# DualUSB2_0_CON.net
KiCad netlist of a schematic drawn in Altium Designer
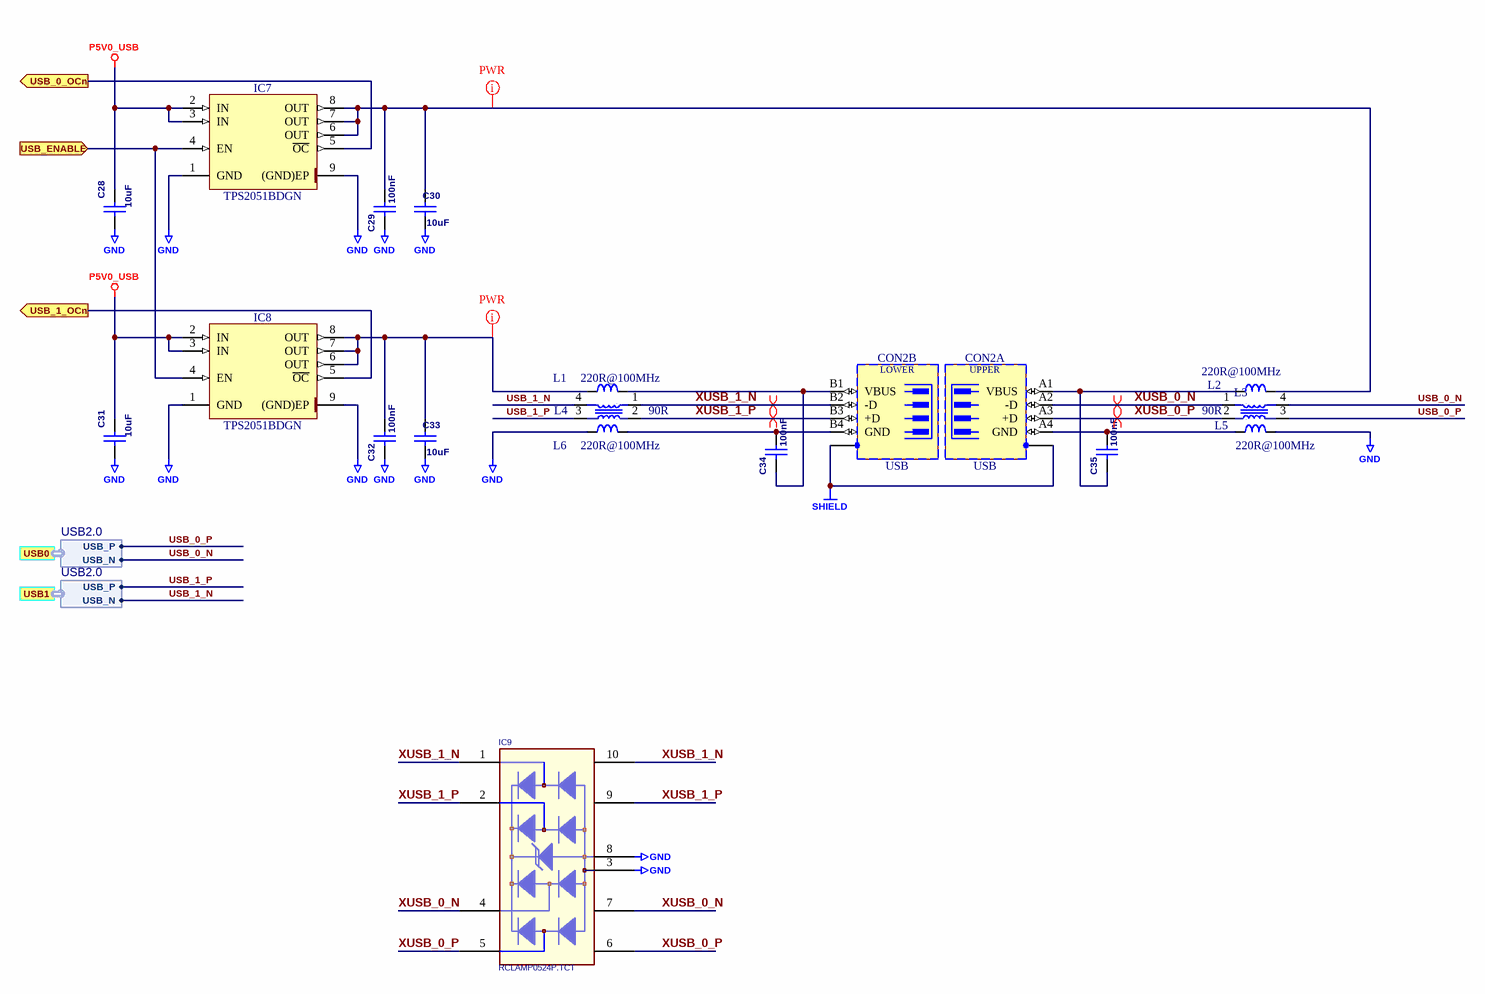
[diagram p0: DualUSB2.0_CON.SchDoc]

(export (version "E")
  (design (tool "Eeschema 10.0.6"))
  (components
    (comp (ref "C28")
      (value "10uF")
      (footprint "CAPC2012X135N")
      (description "Non-polarised capacitor")
      (fields
        (field (name "PART NUMBER") "CC0805_10UF_10V_10%_X7R")
        (field (name "VOLTAGE") "10V")
        (field (name "AUTHOR") "CERN DEM JLC")
      )
      (libsource (lib "Capacitors") (part "Capacitor - non polarized"))
    )
    (comp (ref "C29")
      (value "100nF")
      (footprint "CAPC1005X55N")
      (description "Non-polarised capacitor")
      (fields
        (field (name "PART NUMBER") "CC0402_100NF_16V_10%_X7R")
        (field (name "VOLTAGE") "16V")
        (field (name "AUTHOR") "CERN DEM JLC")
      )
      (libsource (lib "Capacitors") (part "Capacitor - non polarized"))
    )
    (comp (ref "C30")
      (value "10uF")
      (footprint "CAPC2012X135N")
      (description "Non-polarised capacitor")
      (fields
        (field (name "PART NUMBER") "CC0805_10UF_10V_10%_X7R")
        (field (name "VOLTAGE") "10V")
        (field (name "AUTHOR") "CERN DEM JLC")
      )
      (libsource (lib "Capacitors") (part "Capacitor - non polarized"))
    )
    (comp (ref "C31")
      (value "10uF")
      (footprint "CAPC2012X135N")
      (description "Non-polarised capacitor")
      (fields
        (field (name "PART NUMBER") "CC0805_10UF_10V_10%_X7R")
        (field (name "VOLTAGE") "10V")
        (field (name "AUTHOR") "CERN DEM JLC")
      )
      (libsource (lib "Capacitors") (part "Capacitor - non polarized"))
    )
    (comp (ref "C32")
      (value "100nF")
      (footprint "CAPC1005X55N")
      (description "Non-polarised capacitor")
      (fields
        (field (name "PART NUMBER") "CC0402_100NF_16V_10%_X7R")
        (field (name "VOLTAGE") "16V")
        (field (name "AUTHOR") "CERN DEM JLC")
      )
      (libsource (lib "Capacitors") (part "Capacitor - non polarized"))
    )
    (comp (ref "C33")
      (value "10uF")
      (footprint "CAPC2012X135N")
      (description "Non-polarised capacitor")
      (fields
        (field (name "PART NUMBER") "CC0805_10UF_10V_10%_X7R")
        (field (name "VOLTAGE") "10V")
        (field (name "AUTHOR") "CERN DEM JLC")
      )
      (libsource (lib "Capacitors") (part "Capacitor - non polarized"))
    )
    (comp (ref "C34")
      (value "100nF")
      (footprint "CAPC1005X55N")
      (description "Non-polarised capacitor")
      (fields
        (field (name "PART NUMBER") "CC0402_100NF_16V_10%_X7R")
        (field (name "VOLTAGE") "16V")
        (field (name "AUTHOR") "CERN DEM JLC")
      )
      (libsource (lib "Capacitors") (part "Capacitor - non polarized"))
    )
    (comp (ref "C35")
      (value "100nF")
      (footprint "CAPC1005X55N")
      (description "Non-polarised capacitor")
      (fields
        (field (name "PART NUMBER") "CC0402_100NF_16V_10%_X7R")
        (field (name "VOLTAGE") "16V")
        (field (name "AUTHOR") "CERN DEM JLC")
      )
      (libsource (lib "Capacitors") (part "Capacitor - non polarized"))
    )
    (comp (ref "CON2")
      (value "USB")
      (footprint "FCI_72309-8034BLF")
      (description "Dual 4 Pin + 1 Shield USB Receptacle")
      (fields
        (field (name "PART NUMBER") "FCI_72309-8034BLF")
        (field (name "MANUFACTURER") "FCI")
        (field (name "AUTHOR") "CERN DEM JLC")
      )
      (libsource (lib "Connectors") (part "Connector USBx2 4 Pin + 1Shield"))
    )
    (comp (ref "IC7")
      (value "TPS2051BDGN")
      (footprint "SOP65P490X110-9N-R157X189")
      (description "One Channel, Current-Limited, Power-Distribution Switches")
      (fields (field (name "MANUFACTURER") "TEXAS INSTRUMENTS") (field (name "AUTHOR") "CERN DEM BC"))
      (libsource (lib "ICs And Semiconductors") (part "TPS2051BDGN"))
    )
    (comp (ref "IC8")
      (value "TPS2051BDGN")
      (footprint "SOP65P490X110-9N-R157X189")
      (description "One Channel, Current-Limited, Power-Distribution Switches")
      (fields (field (name "MANUFACTURER") "TEXAS INSTRUMENTS") (field (name "AUTHOR") "CERN DEM BC"))
      (libsource (lib "ICs And Semiconductors") (part "TPS2051BDGN"))
    )
    (comp (ref "IC9")
      (value "RCLAMP0524P.TCT")
      (description "DIODE,RCLAMP0524P,SEMTECH")
      (libsource (lib "LIBRARY_SCH") (part "D_TVS_RCLAMP0524P"))
    )
    (comp (ref "L1")
      (value "220R@100MHz")
      (footprint "INDC2012X105N")
      (description "Inductor")
      (fields
        (field (name "PART NUMBER") "IND0805_MURATA_BLM21PG221SN1D")
        (field (name "POWER") "2A")
        (field (name "AUTHOR") "CERN DEM JLC")
      )
      (libsource (lib "Inductors & Transformers") (part "Inductor"))
    )
    (comp (ref "L2")
      (value "220R@100MHz")
      (footprint "INDC2012X105N")
      (description "Inductor")
      (fields
        (field (name "PART NUMBER") "IND0805_MURATA_BLM21PG221SN1D")
        (field (name "POWER") "2A")
        (field (name "AUTHOR") "CERN DEM JLC")
      )
      (libsource (lib "Inductors & Transformers") (part "Inductor"))
    )
    (comp (ref "L3")
      (value "90R")
      (footprint "DLSCM0805")
      (description "Common Mode Choke 90R")
      (fields (field (name "Comment") "DLSCM0805-900M or DLW21SN900SQ2L"))
      (libsource (lib "") (part "L_CMC_DLSCM0805_90R_1"))
    )
    (comp (ref "L4")
      (value "90R")
      (footprint "DLSCM0805")
      (description "Common Mode Choke 90R")
      (fields (field (name "Comment") "DLSCM0805-900M or DLW21SN900SQ2L"))
      (libsource (lib "LIBRARY_SCH") (part "L_CMC_DLSCM0805_90R"))
    )
    (comp (ref "L5")
      (value "220R@100MHz")
      (footprint "INDC2012X105N")
      (description "Inductor")
      (fields
        (field (name "PART NUMBER") "IND0805_MURATA_BLM21PG221SN1D")
        (field (name "POWER") "2A")
        (field (name "AUTHOR") "CERN DEM JLC")
      )
      (libsource (lib "Inductors & Transformers") (part "Inductor"))
    )
    (comp (ref "L6")
      (value "220R@100MHz")
      (footprint "INDC2012X105N")
      (description "Inductor")
      (fields
        (field (name "PART NUMBER") "IND0805_MURATA_BLM21PG221SN1D")
        (field (name "POWER") "2A")
        (field (name "AUTHOR") "CERN DEM JLC")
      )
      (libsource (lib "Inductors & Transformers") (part "Inductor"))
    )
  )
  (nets
    (net (code "2") (name "/USB_0_N") (class "Default")
      (node (ref "L3") (pin "4") (pinfunction "4_4") (pintype "passive"))
    )
    (net (code "3") (name "/USB_0_OCn") (class "Default")
      (node (ref "IC7") (pin "5") (pinfunction "~{OC}_5") (pintype "output"))
    )
    (net (code "4") (name "/USB_0_P") (class "Default")
      (node (ref "L3") (pin "3") (pinfunction "3_3") (pintype "passive"))
    )
    (net (code "5") (name "/USB_1_N") (class "Default")
      (node (ref "L4") (pin "4") (pinfunction "4_4") (pintype "passive"))
    )
    (net (code "6") (name "/USB_1_OCn") (class "Default")
      (node (ref "IC8") (pin "5") (pinfunction "~{OC}_5") (pintype "output"))
    )
    (net (code "7") (name "/USB_1_P") (class "Default")
      (node (ref "L4") (pin "3") (pinfunction "3_3") (pintype "passive"))
    )
    (net (code "8") (name "/USB_ENABLE") (class "Default")
      (node (ref "IC7") (pin "4") (pinfunction "EN_4") (pintype "input"))
      (node (ref "IC8") (pin "4") (pinfunction "EN_4") (pintype "input"))
    )
    (net (code "9") (name "/XUSB_0_N") (class "Default")
      (node (ref "CON2") (pin "A2") (pinfunction "-D_A2") (pintype "bidirectional"))
      (node (ref "IC9") (pin "4") (pinfunction "4_4") (pintype "passive"))
      (node (ref "IC9") (pin "7") (pinfunction "7_7") (pintype "passive"))
      (node (ref "L3") (pin "1") (pinfunction "1_1") (pintype "passive"))
    )
    (net (code "10") (name "/XUSB_0_P") (class "Default")
      (node (ref "CON2") (pin "A3") (pinfunction "+D_A3") (pintype "bidirectional"))
      (node (ref "IC9") (pin "5") (pinfunction "5_5") (pintype "passive"))
      (node (ref "IC9") (pin "6") (pinfunction "6_6") (pintype "passive"))
      (node (ref "L3") (pin "2") (pinfunction "2_2") (pintype "passive"))
    )
    (net (code "11") (name "/XUSB_1_N") (class "Default")
      (node (ref "CON2") (pin "B2") (pinfunction "-D_B2") (pintype "bidirectional"))
      (node (ref "IC9") (pin "1") (pinfunction "1_1") (pintype "passive"))
      (node (ref "IC9") (pin "10") (pinfunction "10_10") (pintype "passive"))
      (node (ref "L4") (pin "1") (pinfunction "1_1") (pintype "passive"))
    )
    (net (code "12") (name "/XUSB_1_P") (class "Default")
      (node (ref "CON2") (pin "B3") (pinfunction "+D_B3") (pintype "bidirectional"))
      (node (ref "IC9") (pin "2") (pinfunction "2_2") (pintype "passive"))
      (node (ref "IC9") (pin "9") (pinfunction "9_9") (pintype "passive"))
      (node (ref "L4") (pin "2") (pinfunction "2_2") (pintype "passive"))
    )
    (net (code "14") (name "GND") (class "Default")
      (node (ref "C28") (pin "1") (pinfunction "1_1") (pintype "passive"))
      (node (ref "C29") (pin "1") (pinfunction "1_1") (pintype "passive"))
      (node (ref "C30") (pin "1") (pinfunction "1_1") (pintype "passive"))
      (node (ref "C31") (pin "1") (pinfunction "1_1") (pintype "passive"))
      (node (ref "C32") (pin "1") (pinfunction "1_1") (pintype "passive"))
      (node (ref "C33") (pin "1") (pinfunction "1_1") (pintype "passive"))
      (node (ref "IC7") (pin "1") (pinfunction "GND_1") (pintype "power_in"))
      (node (ref "IC7") (pin "9") (pinfunction "(GND)EP_9") (pintype "power_in"))
      (node (ref "IC8") (pin "1") (pinfunction "GND_1") (pintype "power_in"))
      (node (ref "IC8") (pin "9") (pinfunction "(GND)EP_9") (pintype "power_in"))
      (node (ref "IC9") (pin "3") (pinfunction "3_3") (pintype "passive"))
      (node (ref "IC9") (pin "8") (pinfunction "8_8") (pintype "passive"))
      (node (ref "L5") (pin "2") (pinfunction "2_2") (pintype "passive"))
      (node (ref "L6") (pin "1") (pinfunction "1_1") (pintype "passive"))
    )
    (net (code "15") (name "Net-(C29-Pad2)") (class "Default")
      (node (ref "C29") (pin "2") (pinfunction "2_2") (pintype "passive"))
      (node (ref "C30") (pin "2") (pinfunction "2_2") (pintype "passive"))
      (node (ref "IC7") (pin "6") (pinfunction "OUT_6") (pintype "output"))
      (node (ref "IC7") (pin "7") (pinfunction "OUT_7") (pintype "output"))
      (node (ref "IC7") (pin "8") (pinfunction "OUT_8") (pintype "output"))
      (node (ref "L2") (pin "2") (pinfunction "2_2") (pintype "passive"))
    )
    (net (code "16") (name "Net-(C32-Pad2)") (class "Default")
      (node (ref "C32") (pin "2") (pinfunction "2_2") (pintype "passive"))
      (node (ref "C33") (pin "2") (pinfunction "2_2") (pintype "passive"))
      (node (ref "IC8") (pin "6") (pinfunction "OUT_6") (pintype "output"))
      (node (ref "IC8") (pin "7") (pinfunction "OUT_7") (pintype "output"))
      (node (ref "IC8") (pin "8") (pinfunction "OUT_8") (pintype "output"))
      (node (ref "L1") (pin "1") (pinfunction "1_1") (pintype "passive"))
    )
    (net (code "17") (name "Net-(CON2A-GND)") (class "Default")
      (node (ref "C35") (pin "2") (pinfunction "2_2") (pintype "passive"))
      (node (ref "CON2") (pin "A4") (pinfunction "GND_A4") (pintype "bidirectional"))
      (node (ref "L5") (pin "1") (pinfunction "1_1") (pintype "passive"))
    )
    (net (code "18") (name "Net-(CON2A-VBUS)") (class "Default")
      (node (ref "C35") (pin "1") (pinfunction "1_1") (pintype "passive"))
      (node (ref "CON2") (pin "A1") (pinfunction "VBUS_A1") (pintype "bidirectional"))
      (node (ref "L2") (pin "1") (pinfunction "1_1") (pintype "passive"))
    )
    (net (code "19") (name "Net-(CON2B-GND)") (class "Default")
      (node (ref "C34") (pin "2") (pinfunction "2_2") (pintype "passive"))
      (node (ref "CON2") (pin "B4") (pinfunction "GND_B4") (pintype "bidirectional"))
      (node (ref "L6") (pin "2") (pinfunction "2_2") (pintype "passive"))
    )
    (net (code "20") (name "Net-(CON2B-VBUS)") (class "Default")
      (node (ref "C34") (pin "1") (pinfunction "1_1") (pintype "passive"))
      (node (ref "CON2") (pin "B1") (pinfunction "VBUS_B1") (pintype "bidirectional"))
      (node (ref "L1") (pin "2") (pinfunction "2_2") (pintype "passive"))
    )
    (net (code "21") (name "P5V0_USB") (class "Default")
      (node (ref "C28") (pin "2") (pinfunction "2_2") (pintype "passive"))
      (node (ref "C31") (pin "2") (pinfunction "2_2") (pintype "passive"))
      (node (ref "IC7") (pin "2") (pinfunction "IN_2") (pintype "input"))
      (node (ref "IC7") (pin "3") (pinfunction "IN_3") (pintype "input"))
      (node (ref "IC8") (pin "2") (pinfunction "IN_2") (pintype "input"))
      (node (ref "IC8") (pin "3") (pinfunction "IN_3") (pintype "input"))
    )
    (net (code "22") (name "SHIELD") (class "Default")
      (node (ref "CON2") (pin "SH") (pinfunction "SHIELD_SH") (pintype "power_in"))
    )
  )
)
